# Sensors.net
KiCad netlist of a schematic drawn in Altium Designer
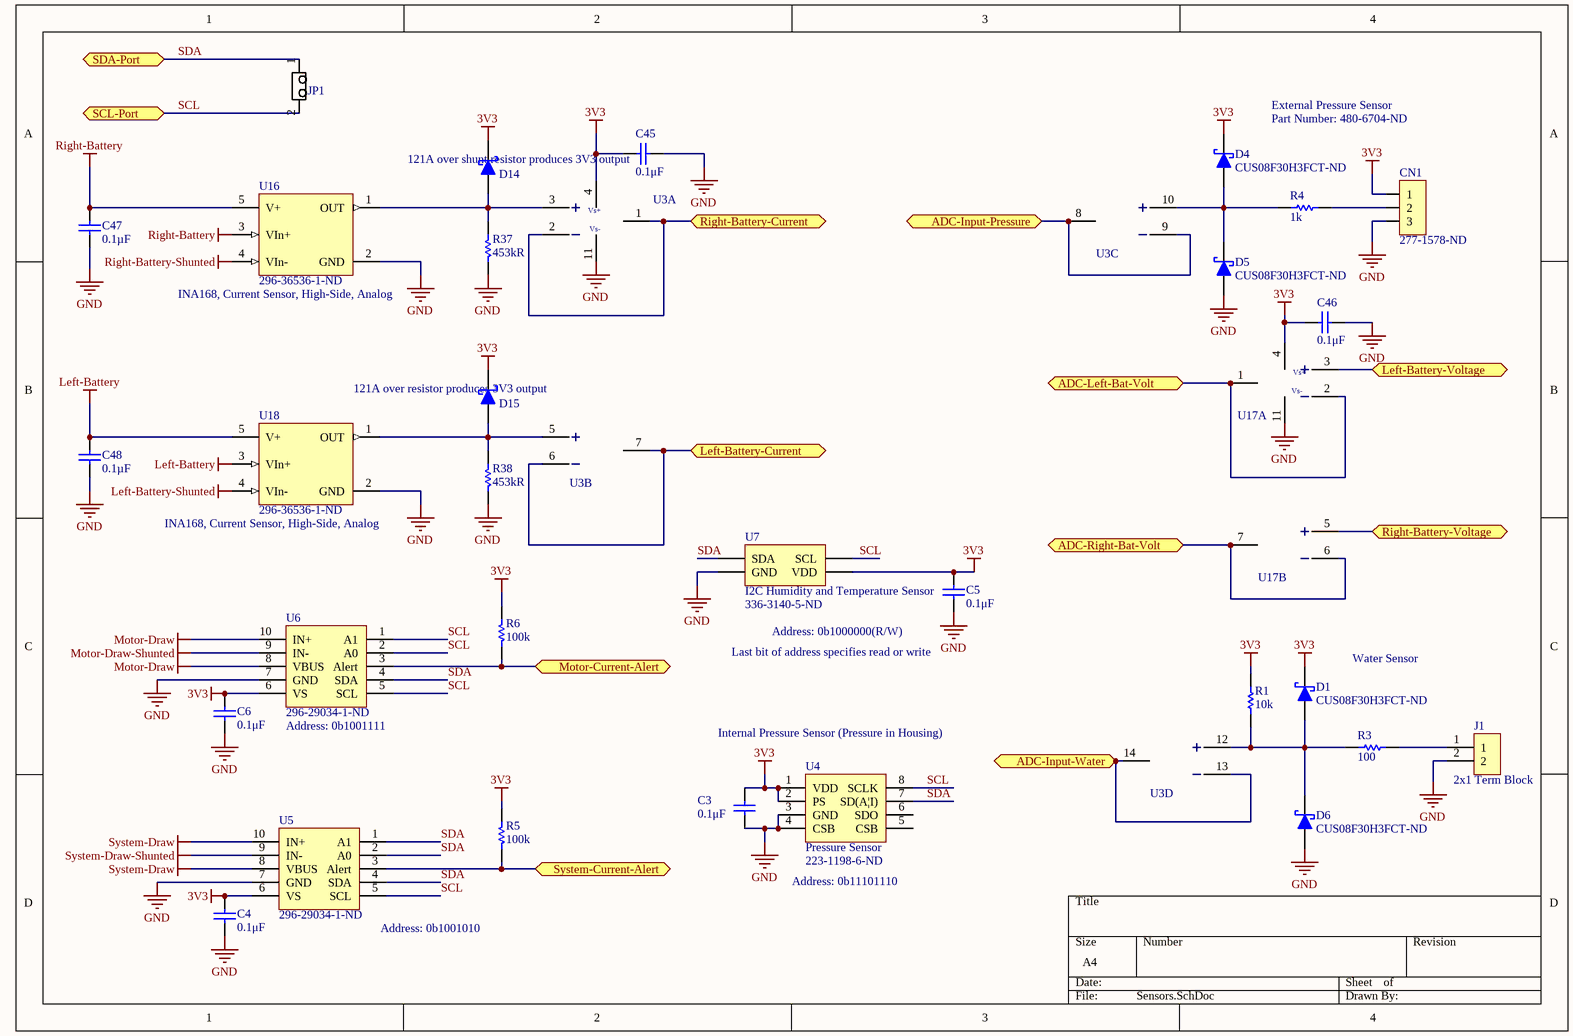
[diagram p0: Sensors.SchDoc]

(export (version "E")
  (design (tool "Eeschema 10.0.6"))
  (components
    (comp (ref "C3")
      (value "0.1μF")
      (footprint "CAPC1608N(0603\")")
      (description "Capacitor, Ceramic, 100V, +/- 10%, 0603 SMD, X7R")
      (fields
        (field (name "MFG") "TDK")
        (field (name "PUBLISHER") "AUVic")
        (field (name "CREATED BY") "Ashwin Sira")
      )
      (libsource (lib "AUVic_Integrated_Library_Capacitors") (part "0.1uF 100V 0603 SMD, Ceramic"))
    )
    (comp (ref "C4")
      (value "0.1μF")
      (footprint "CAPC1608N(0603\")")
      (description "Capacitor, Ceramic, 100V, +/- 10%, 0603 SMD, X7R")
      (fields
        (field (name "MFG") "TDK")
        (field (name "PUBLISHER") "AUVic")
        (field (name "CREATED BY") "Ashwin Sira")
      )
      (libsource (lib "AUVic_Integrated_Library_Capacitors") (part "0.1uF 100V 0603 SMD, Ceramic"))
    )
    (comp (ref "C5")
      (value "0.1μF")
      (footprint "CAPC1608N(0603\")")
      (description "Capacitor, Ceramic, 100V, +/- 10%, 0603 SMD, X7R")
      (fields
        (field (name "MFG") "TDK")
        (field (name "PUBLISHER") "AUVic")
        (field (name "CREATED BY") "Ashwin Sira")
      )
      (libsource (lib "AUVic_Integrated_Library_Capacitors") (part "0.1uF 100V 0603 SMD, Ceramic"))
    )
    (comp (ref "C6")
      (value "0.1μF")
      (footprint "CAPC1608N(0603\")")
      (description "Capacitor, Ceramic, 100V, +/- 10%, 0603 SMD, X7R")
      (fields
        (field (name "MFG") "TDK")
        (field (name "PUBLISHER") "AUVic")
        (field (name "CREATED BY") "Ashwin Sira")
      )
      (libsource (lib "AUVic_Integrated_Library_Capacitors") (part "0.1uF 100V 0603 SMD, Ceramic"))
    )
    (comp (ref "C45")
      (value "0.1μF")
      (footprint "CAPC1608N(0603\")")
      (description "Capacitor, Ceramic, 16V, +/- 10%, 0603 SMD, X7R")
      (fields (field (name "PUBLISHER") "AUVic") (field (name "CREATED BY") "Andy Bates"))
      (libsource (lib "AUVic_Integrated_Library_Capacitors") (part "0.1uF 16V 0603 SMD, Ceramic"))
    )
    (comp (ref "C46")
      (value "0.1μF")
      (footprint "CAPC1608N(0603\")")
      (description "Capacitor, Ceramic, 16V, +/- 10%, 0603 SMD, X7R")
      (fields (field (name "PUBLISHER") "AUVic") (field (name "CREATED BY") "Andy Bates"))
      (libsource (lib "AUVic_Integrated_Library_Capacitors") (part "0.1uF 16V 0603 SMD, Ceramic"))
    )
    (comp (ref "C47")
      (value "0.1µF")
      (footprint "CAPC2012N(0805\")")
      (description "Capacitor, Ceramic, 50V, +/-5%, 0805 SMD, X7R")
      (fields (field (name "PUBLISHER") "AUVic"))
      (libsource (lib "AUVic_Integrated_Library_Capacitors") (part "0.1uF 50V 0805 SMD, Ceramic"))
    )
    (comp (ref "C48")
      (value "0.1µF")
      (footprint "CAPC2012N(0805\")")
      (description "Capacitor, Ceramic, 50V, +/-5%, 0805 SMD, X7R")
      (fields (field (name "PUBLISHER") "AUVic"))
      (libsource (lib "AUVic_Integrated_Library_Capacitors") (part "0.1uF 50V 0805 SMD, Ceramic"))
    )
    (comp (ref "CN1")
      (value "3x1, Terminal Block, Pitch: 5mm, Screw, THT")
      (footprint "3x1, Terminal Block, Pitch: 5mm, Screw, THT")
      (fields
        (field (name "SUPPLIER PART NUMBER 1") "277-1578-ND")
        (field (name "PUBLISHER") "AUVic, Ashwin Sira")
        (field (name "REVIEWED BY") "*")
      )
      (libsource (lib "AUVic_Integrated_Library_Connectors") (part "3x1, Terminal Block, Pitch{colon} 5mm, Screw, THT"))
    )
    (comp (ref "D1")
      (value "CUS08F30H3FCT-ND")
      (footprint "SC-76")
      (description "Diode, Schottky, 30V, 800mA")
      (fields
        (field (name "SUPPLIER PART NUMBER 1") "CUS08F30H3FCT-ND")
        (field (name "CREATED BY") "Andy Bates")
        (field (name "PUBLISHER") "AUVic")
      )
      (libsource (lib "AUVic_Integrated_Library_Diodes") (part "CUS08F30H3FCT-ND"))
    )
    (comp (ref "D4")
      (value "CUS08F30H3FCT-ND")
      (footprint "SC-76")
      (description "Diode, Schottky, 30V, 800mA")
      (fields
        (field (name "SUPPLIER PART NUMBER 1") "CUS08F30H3FCT-ND")
        (field (name "CREATED BY") "Andy Bates")
        (field (name "PUBLISHER") "AUVic")
      )
      (libsource (lib "AUVic_Integrated_Library_Diodes") (part "CUS08F30H3FCT-ND"))
    )
    (comp (ref "D5")
      (value "CUS08F30H3FCT-ND")
      (footprint "SC-76")
      (description "Diode, Schottky, 30V, 800mA")
      (fields
        (field (name "SUPPLIER PART NUMBER 1") "CUS08F30H3FCT-ND")
        (field (name "CREATED BY") "Andy Bates")
        (field (name "PUBLISHER") "AUVic")
      )
      (libsource (lib "AUVic_Integrated_Library_Diodes") (part "CUS08F30H3FCT-ND"))
    )
    (comp (ref "D6")
      (value "CUS08F30H3FCT-ND")
      (footprint "SC-76")
      (description "Diode, Schottky, 30V, 800mA")
      (fields
        (field (name "SUPPLIER PART NUMBER 1") "CUS08F30H3FCT-ND")
        (field (name "CREATED BY") "Andy Bates")
        (field (name "PUBLISHER") "AUVic")
      )
      (libsource (lib "AUVic_Integrated_Library_Diodes") (part "CUS08F30H3FCT-ND"))
    )
    (comp (ref "D14")
      (value "DB2J31400L")
      (footprint "SODFL250X80-2N")
      (description "Diode, Schottky, 20V, 30mA")
      (fields (field (name "CREATED BY") "Ashwin Sira") (field (name "PUBLISHER") "AUVic"))
      (libsource (lib "AUVic_Integrated_Library_Diodes") (part "DB2J31400L"))
    )
    (comp (ref "D15")
      (value "DB2J31400L")
      (footprint "SODFL250X80-2N")
      (description "Diode, Schottky, 20V, 30mA")
      (fields (field (name "CREATED BY") "Ashwin Sira") (field (name "PUBLISHER") "AUVic"))
      (libsource (lib "AUVic_Integrated_Library_Diodes") (part "DB2J31400L"))
    )
    (comp (ref "J1")
      (value "2x1 Term Block")
      (footprint "2X1 Terminal Blocks")
      (fields (field (name "MADE BY") "Andy Bates"))
      (libsource (lib "AUVic_Integrated_Library_Connectors") (part "2x1 Terminal Block"))
    )
    (comp (ref "JP1")
      (value "1X2 Pin Head")
      (footprint "2X1 Males Header")
      (fields (field (name "MADE BY") "Andy Bates"))
      (libsource (lib "AUVic_Integrated_Library_Connectors") (part "1x2 Male Header"))
    )
    (comp (ref "R1")
      (value "10k")
      (footprint "RESC1608N(0603\")")
      (description "10kR, 1%, 1/10W, 0603 SMD")
      (fields (field (name "MADE BY") "Ashwin Sira"))
      (libsource (lib "AUVic_Integrated_Library_Resistors") (part "10kR, 1%, 1/10W, 0603 SMD"))
    )
    (comp (ref "R3")
      (value "100")
      (footprint "RESC1608N(0603\")")
      (description "100R, 1%, 1/10W, 0603 SMD")
      (fields (field (name "MADE BY") "Andy Bates"))
      (libsource (lib "AUVic_Integrated_Library_Resistors") (part "100R, 1%, 1/10W, 0603 SMD"))
    )
    (comp (ref "R4")
      (value "1k")
      (footprint "RESC1608N(0603\")")
      (description "1kR, 1%, 1/10W , 0603, SMD")
      (fields (field (name "CREATED BY") "Andy Bates") (field (name "PUBLISHER") "AUVic"))
      (libsource (lib "AUVic_Integrated_Library_Resistors") (part "1kR, 1%, 1/10W , 0603, SMD"))
    )
    (comp (ref "R5")
      (value "100k")
      (footprint "RESC2012N(0805\")")
      (description "100kR, 1%, 1/4W, 0805 SMD")
      (fields (field (name "MADE BY") "Ashwin Sira"))
      (libsource (lib "AUVic_Integrated_Library_Resistors") (part "100kR, 1%, 1/4W, 0805 SMD"))
    )
    (comp (ref "R6")
      (value "100k")
      (footprint "RESC2012N(0805\")")
      (description "100kR, 1%, 1/4W, 0805 SMD")
      (fields (field (name "MADE BY") "Ashwin Sira"))
      (libsource (lib "AUVic_Integrated_Library_Resistors") (part "100kR, 1%, 1/4W, 0805 SMD"))
    )
    (comp (ref "R37")
      (value "453kR")
      (footprint "RESC1608N(0603\")")
      (description "453kR, 1%, 1/10W, 0603 SMD")
      (fields (field (name "CREATED BY") "Lyden Smith"))
      (libsource (lib "AUVic_Integrated_Library_Resistors") (part "453kR, 1%, 1/10W, 0603 SMD_1"))
    )
    (comp (ref "R38")
      (value "453kR")
      (footprint "RESC1608N(0603\")")
      (description "453kR, 1%, 1/10W, 0603 SMD")
      (fields (field (name "CREATED BY") "Lyden Smith"))
      (libsource (lib "AUVic_Integrated_Library_Resistors") (part "453kR, 1%, 1/10W, 0603 SMD_1"))
    )
    (comp (ref "U3")
      (value "Quad Op Amp LMV324LIPT")
      (footprint "TSSOP14")
      (description "LM324")
      (fields (field (name "CREATED BY") "Silvano"))
      (libsource (lib "AUVic_Integrated_Library_Op_amps") (part "Quad Op Amp LMV324LIPT"))
    )
    (comp (ref "U4")
      (value "Pressure Sensor")
      (footprint "TE Pressure Sensor (MS560702BA03-50)")
      (description "1kPa to 120 kPa")
      (fields (field (name "SUPPLIER PART NUMBER 1") "223-1198-6-ND") (field (name "MADE BY") "Andy Bates"))
      (libsource (lib "AUVic_Integrated_Library_Sensors") (part "MS560702BA03-50 Pressure Sensor"))
    )
    (comp (ref "U5")
      (value "High side current sensor")
      (footprint "MSOP-10")
      (description "0-36V High side current sensor")
      (fields (field (name "SUPPLIER PART NUMBER 2") "296-29034-1-ND") (field (name "MADE BY") "Andy Bates"))
      (libsource (lib "AUVic_Integrated_Library_Sensors") (part "INA226AIDGSR, Current Sensor, High Side"))
    )
    (comp (ref "U6")
      (value "High side current sensor")
      (footprint "MSOP-10")
      (description "0-36V High side current sensor")
      (fields (field (name "SUPPLIER PART NUMBER 2") "296-29034-1-ND") (field (name "MADE BY") "Andy Bates"))
      (libsource (lib "AUVic_Integrated_Library_Sensors") (part "INA226AIDGSR, Current Sensor, High Side"))
    )
    (comp (ref "U7")
      (value "I2C Humidity and Temperature Sensor")
      (footprint "QFN-6")
      (fields (field (name "SUPPLIER PART NUMBER 1") "336-3140-5-ND") (field (name "MADE BY") "Andy Bates"))
      (libsource (lib "AUVic_Integrated_Library_Sensors") (part "Si700XX"))
    )
    (comp (ref "U16")
      (value "INA168, Current Sensor, High-Side, Analog")
      (footprint "SOT23-5")
      (fields
        (field (name "SUPPLIER PART NUMBER 1") "296-36536-1-ND")
        (field (name "CREATED BY") "Jacob Lower")
        (field (name "PUBLISHER") "AUVic")
      )
      (libsource (lib "AUVic_Integrated_Library_Sensors") (part "INA168, Current Sensor, High-Side, Analog"))
    )
    (comp (ref "U17")
      (value "Quad Op Amp LMV324LIPT")
      (footprint "TSSOP14")
      (description "LM324")
      (fields (field (name "CREATED BY") "Silvano"))
      (libsource (lib "AUVic_Integrated_Library_Op_amps") (part "Quad Op Amp LMV324LIPT"))
    )
    (comp (ref "U18")
      (value "INA168, Current Sensor, High-Side, Analog")
      (footprint "SOT23-5")
      (fields
        (field (name "SUPPLIER PART NUMBER 1") "296-36536-1-ND")
        (field (name "CREATED BY") "Jacob Lower")
        (field (name "PUBLISHER") "AUVic")
      )
      (libsource (lib "AUVic_Integrated_Library_Sensors") (part "INA168, Current Sensor, High-Side, Analog"))
    )
  )
  (nets
    (net (code "1") (name "/ADC-Input-Pressure") (class "Default")
      (node (ref "U3") (pin "8") (pinfunction "Output_3_8") (pintype "passive"))
      (node (ref "U3") (pin "9") (pinfunction "Inverting_Input_3_9") (pintype "passive"))
    )
    (net (code "2") (name "/ADC-Input-Water") (class "Default")
      (node (ref "U3") (pin "13") (pinfunction "Inverting_Input_3_13") (pintype "passive"))
      (node (ref "U3") (pin "14") (pinfunction "Output_4_14") (pintype "passive"))
    )
    (net (code "3") (name "/ADC-Left-Bat-Volt") (class "Default")
      (node (ref "U17") (pin "1") (pinfunction "Output_1_1") (pintype "passive"))
      (node (ref "U17") (pin "2") (pinfunction "Inverting_Input_1_2") (pintype "passive"))
    )
    (net (code "4") (name "/ADC-Right-Bat-Volt") (class "Default")
      (node (ref "U17") (pin "6") (pinfunction "Inverting_Input_2_6") (pintype "passive"))
      (node (ref "U17") (pin "7") (pinfunction "Output_2_7") (pintype "passive"))
    )
    (net (code "5") (name "/Left-Battery-Current") (class "Default")
      (node (ref "U3") (pin "6") (pinfunction "Inverting_Input_2_6") (pintype "passive"))
      (node (ref "U3") (pin "7") (pinfunction "Output_2_7") (pintype "passive"))
    )
    (net (code "6") (name "/Left-Battery-Voltage") (class "Default")
      (node (ref "U17") (pin "3") (pinfunction "Non-Inverting_Input_1_3") (pintype "passive"))
    )
    (net (code "7") (name "/Motor-Current-Alert") (class "Default")
      (node (ref "R6") (pin "1") (pinfunction "1_1") (pintype "passive"))
      (node (ref "U6") (pin "3") (pinfunction "Alert_3") (pintype "passive"))
    )
    (net (code "8") (name "/Right-Battery-Current") (class "Default")
      (node (ref "U3") (pin "1") (pinfunction "Output_1_1") (pintype "passive"))
      (node (ref "U3") (pin "2") (pinfunction "Inverting_Input_1_2") (pintype "passive"))
    )
    (net (code "9") (name "/Right-Battery-Voltage") (class "Default")
      (node (ref "U17") (pin "5") (pinfunction "Non-Inverting_Input_2_5") (pintype "passive"))
    )
    (net (code "10") (name "/SCL") (class "Default")
      (node (ref "JP1") (pin "2") (pinfunction "2_2") (pintype "passive"))
      (node (ref "U4") (pin "8") (pinfunction "SCLK_8") (pintype "passive"))
      (node (ref "U5") (pin "5") (pinfunction "SCL_5") (pintype "passive"))
      (node (ref "U6") (pin "1") (pinfunction "A1_1") (pintype "passive"))
      (node (ref "U6") (pin "2") (pinfunction "A0_2") (pintype "passive"))
      (node (ref "U6") (pin "5") (pinfunction "SCL_5") (pintype "passive"))
      (node (ref "U7") (pin "6") (pinfunction "SCL_6") (pintype "passive"))
    )
    (net (code "11") (name "/SDA") (class "Default")
      (node (ref "JP1") (pin "1") (pinfunction "1_1") (pintype "passive"))
      (node (ref "U4") (pin "7") (pinfunction "SD(A¦I)_7") (pintype "passive"))
      (node (ref "U5") (pin "1") (pinfunction "A1_1") (pintype "passive"))
      (node (ref "U5") (pin "2") (pinfunction "A0_2") (pintype "passive"))
      (node (ref "U5") (pin "4") (pinfunction "SDA_4") (pintype "passive"))
      (node (ref "U6") (pin "4") (pinfunction "SDA_4") (pintype "passive"))
      (node (ref "U7") (pin "1") (pinfunction "SDA_1") (pintype "passive"))
    )
    (net (code "12") (name "/System-Current-Alert") (class "Default")
      (node (ref "R5") (pin "1") (pinfunction "1_1") (pintype "passive"))
      (node (ref "U5") (pin "3") (pinfunction "Alert_3") (pintype "passive"))
    )
    (net (code "13") (name "3V3") (class "Default")
      (node (ref "C3") (pin "2") (pinfunction "Cathode_2") (pintype "passive"))
      (node (ref "C4") (pin "2") (pinfunction "Cathode_2") (pintype "passive"))
      (node (ref "C45") (pin "2") (pinfunction "Cathode_2") (pintype "passive"))
      (node (ref "C46") (pin "2") (pinfunction "Cathode_2") (pintype "passive"))
      (node (ref "C5") (pin "2") (pinfunction "Cathode_2") (pintype "passive"))
      (node (ref "C6") (pin "2") (pinfunction "Cathode_2") (pintype "passive"))
      (node (ref "CN1") (pin "1") (pinfunction "1_1") (pintype "passive"))
      (node (ref "D1") (pin "K") (pinfunction "Cathode_K") (pintype "passive"))
      (node (ref "D14") (pin "1") (pinfunction "Cathode_1") (pintype "passive"))
      (node (ref "D15") (pin "1") (pinfunction "Cathode_1") (pintype "passive"))
      (node (ref "D4") (pin "K") (pinfunction "Cathode_K") (pintype "passive"))
      (node (ref "R1") (pin "2") (pinfunction "2_2") (pintype "passive"))
      (node (ref "R5") (pin "2") (pinfunction "2_2") (pintype "passive"))
      (node (ref "R6") (pin "2") (pinfunction "2_2") (pintype "passive"))
      (node (ref "U17") (pin "4") (pinfunction "Vcc+_4") (pintype "passive"))
      (node (ref "U3") (pin "4") (pinfunction "Vcc+_4") (pintype "passive"))
      (node (ref "U4") (pin "1") (pinfunction "VDD_1") (pintype "passive"))
      (node (ref "U4") (pin "2") (pinfunction "PS_2") (pintype "passive"))
      (node (ref "U5") (pin "6") (pinfunction "VS_6") (pintype "passive"))
      (node (ref "U6") (pin "6") (pinfunction "VS_6") (pintype "passive"))
      (node (ref "U7") (pin "5") (pinfunction "VDD_5") (pintype "passive"))
    )
    (net (code "14") (name "GND") (class "Default")
      (node (ref "C3") (pin "1") (pinfunction "Anode_1") (pintype "passive"))
      (node (ref "C4") (pin "1") (pinfunction "Anode_1") (pintype "passive"))
      (node (ref "C45") (pin "1") (pinfunction "Anode_1") (pintype "passive"))
      (node (ref "C46") (pin "1") (pinfunction "Anode_1") (pintype "passive"))
      (node (ref "C47") (pin "1") (pinfunction "Anode_1") (pintype "passive"))
      (node (ref "C48") (pin "1") (pinfunction "Anode_1") (pintype "passive"))
      (node (ref "C5") (pin "1") (pinfunction "Anode_1") (pintype "passive"))
      (node (ref "C6") (pin "1") (pinfunction "Anode_1") (pintype "passive"))
      (node (ref "CN1") (pin "3") (pinfunction "3_3") (pintype "passive"))
      (node (ref "D5") (pin "A") (pinfunction "Anode_A") (pintype "passive"))
      (node (ref "D6") (pin "A") (pinfunction "Anode_A") (pintype "passive"))
      (node (ref "J1") (pin "2") (pinfunction "2_2") (pintype "passive"))
      (node (ref "R37") (pin "1") (pinfunction "1_1") (pintype "passive"))
      (node (ref "R38") (pin "1") (pinfunction "1_1") (pintype "passive"))
      (node (ref "U16") (pin "2") (pinfunction "GND_2") (pintype "power_in"))
      (node (ref "U17") (pin "11") (pinfunction "Vcc-_11") (pintype "passive"))
      (node (ref "U18") (pin "2") (pinfunction "GND_2") (pintype "power_in"))
      (node (ref "U3") (pin "11") (pinfunction "Vcc-_11") (pintype "passive"))
      (node (ref "U4") (pin "3") (pinfunction "GND_3") (pintype "passive"))
      (node (ref "U4") (pin "4") (pinfunction "CSB_4") (pintype "passive"))
      (node (ref "U5") (pin "7") (pinfunction "GND_7") (pintype "passive"))
      (node (ref "U6") (pin "7") (pinfunction "GND_7") (pintype "passive"))
      (node (ref "U7") (pin "2") (pinfunction "GND_2") (pintype "passive"))
    )
    (net (code "15") (name "Left-Battery") (class "Default")
      (node (ref "C48") (pin "2") (pinfunction "Cathode_2") (pintype "passive"))
      (node (ref "U18") (pin "3") (pinfunction "VIn+_3") (pintype "input"))
      (node (ref "U18") (pin "5") (pinfunction "V+_5") (pintype "power_in"))
    )
    (net (code "16") (name "Left-Battery-Shunted") (class "Default")
      (node (ref "U18") (pin "4") (pinfunction "VIn-_4") (pintype "input"))
    )
    (net (code "17") (name "Motor-Draw") (class "Default")
      (node (ref "U6") (pin "10") (pinfunction "IN+_10") (pintype "passive"))
      (node (ref "U6") (pin "8") (pinfunction "VBUS_8") (pintype "passive"))
    )
    (net (code "18") (name "Motor-Draw-Shunted") (class "Default")
      (node (ref "U6") (pin "9") (pinfunction "IN-_9") (pintype "passive"))
    )
    (net (code "19") (name "Net-(CN1-Pad2)") (class "Default")
      (node (ref "CN1") (pin "2") (pinfunction "2_2") (pintype "passive"))
      (node (ref "R4") (pin "2") (pinfunction "2_2") (pintype "passive"))
    )
    (net (code "20") (name "Net-(D1-Anode)") (class "Default")
      (node (ref "D1") (pin "A") (pinfunction "Anode_A") (pintype "passive"))
      (node (ref "D6") (pin "K") (pinfunction "Cathode_K") (pintype "passive"))
      (node (ref "R1") (pin "1") (pinfunction "1_1") (pintype "passive"))
      (node (ref "R3") (pin "1") (pinfunction "1_1") (pintype "passive"))
      (node (ref "U3") (pin "12") (pinfunction "Non-Inverting_Input_4_12") (pintype "passive"))
    )
    (net (code "21") (name "Net-(D4-Anode)") (class "Default")
      (node (ref "D4") (pin "A") (pinfunction "Anode_A") (pintype "passive"))
      (node (ref "D5") (pin "K") (pinfunction "Cathode_K") (pintype "passive"))
      (node (ref "R4") (pin "1") (pinfunction "1_1") (pintype "passive"))
      (node (ref "U3") (pin "10") (pinfunction "Non-Inverting_Input_3_10") (pintype "passive"))
    )
    (net (code "22") (name "Net-(D14-Anode)") (class "Default")
      (node (ref "D14") (pin "2") (pinfunction "Anode_2") (pintype "passive"))
      (node (ref "R37") (pin "2") (pinfunction "2_2") (pintype "passive"))
      (node (ref "U16") (pin "1") (pinfunction "OUT_1") (pintype "output"))
      (node (ref "U3") (pin "3") (pinfunction "Non-Inverting_Input_1_3") (pintype "passive"))
    )
    (net (code "23") (name "Net-(D15-Anode)") (class "Default")
      (node (ref "D15") (pin "2") (pinfunction "Anode_2") (pintype "passive"))
      (node (ref "R38") (pin "2") (pinfunction "2_2") (pintype "passive"))
      (node (ref "U18") (pin "1") (pinfunction "OUT_1") (pintype "output"))
      (node (ref "U3") (pin "5") (pinfunction "Non-Inverting_Input_2_5") (pintype "passive"))
    )
    (net (code "24") (name "Net-(J1-Pad1)") (class "Default")
      (node (ref "J1") (pin "1") (pinfunction "1_1") (pintype "passive"))
      (node (ref "R3") (pin "2") (pinfunction "2_2") (pintype "passive"))
    )
    (net (code "25") (name "Right-Battery") (class "Default")
      (node (ref "C47") (pin "2") (pinfunction "Cathode_2") (pintype "passive"))
      (node (ref "U16") (pin "3") (pinfunction "VIn+_3") (pintype "input"))
      (node (ref "U16") (pin "5") (pinfunction "V+_5") (pintype "power_in"))
    )
    (net (code "26") (name "Right-Battery-Shunted") (class "Default")
      (node (ref "U16") (pin "4") (pinfunction "VIn-_4") (pintype "input"))
    )
    (net (code "27") (name "System-Draw") (class "Default")
      (node (ref "U5") (pin "10") (pinfunction "IN+_10") (pintype "passive"))
      (node (ref "U5") (pin "8") (pinfunction "VBUS_8") (pintype "passive"))
    )
    (net (code "28") (name "System-Draw-Shunted") (class "Default")
      (node (ref "U5") (pin "9") (pinfunction "IN-_9") (pintype "passive"))
    )
    (net (code "29") (name "unconnected-(U4-CSB-Pad5)") (class "Default")
      (node (ref "U4") (pin "5") (pinfunction "CSB_5") (pintype "passive"))
    )
    (net (code "30") (name "unconnected-(U4-SDO-Pad6)") (class "Default")
      (node (ref "U4") (pin "6") (pinfunction "SDO_6") (pintype "passive"))
    )
  )
)
